# Board_S1_sche.net
KiCad netlist of a schematic drawn in EAGLE
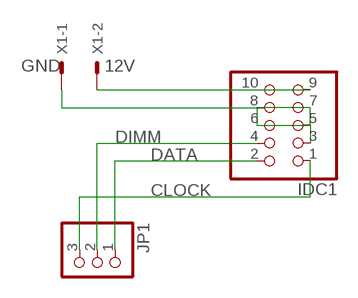
[diagram p0: schematic, sheet 1]

(export (version "E")
  (design (tool "Eeschema 10.0.6"))
  (components
    (comp (ref "IDC1")
      (value "PINHD-2X5")
      (footprint "eagle-import:2X05")
      (libsource (lib "eagle-import") (part "PINHD-2X5"))
    )
    (comp (ref "JP1")
      (value "PINHD-1X3")
      (footprint "eagle-import:1X03")
      (libsource (lib "eagle-import") (part "PINHD-1X3"))
    )
    (comp (ref "X1")
      (value "KK-156-2")
      (footprint "eagle-import:KK-156-2")
      (libsource (lib "eagle-import") (part "KK-156-2"))
    )
  )
  (nets
    (net (code "1") (name "/12V") (class "Default")
      (node (ref "IDC1") (pin "10") (pinfunction "10_10") (pintype "passive"))
      (node (ref "IDC1") (pin "9") (pinfunction "9_9") (pintype "passive"))
      (node (ref "X1") (pin "2") (pinfunction "S_2") (pintype "passive"))
    )
    (net (code "2") (name "/CLOCK") (class "Default")
      (node (ref "IDC1") (pin "1") (pinfunction "1_1") (pintype "passive"))
      (node (ref "JP1") (pin "3") (pinfunction "3_3") (pintype "passive"))
    )
    (net (code "3") (name "/DATA") (class "Default")
      (node (ref "IDC1") (pin "2") (pinfunction "2_2") (pintype "passive"))
      (node (ref "JP1") (pin "1") (pinfunction "1_1") (pintype "passive"))
    )
    (net (code "4") (name "/DIMM") (class "Default")
      (node (ref "IDC1") (pin "4") (pinfunction "4_4") (pintype "passive"))
      (node (ref "JP1") (pin "2") (pinfunction "2_2") (pintype "passive"))
    )
    (net (code "5") (name "/GND") (class "Default")
      (node (ref "IDC1") (pin "3") (pinfunction "3_3") (pintype "passive"))
      (node (ref "IDC1") (pin "5") (pinfunction "5_5") (pintype "passive"))
      (node (ref "IDC1") (pin "6") (pinfunction "6_6") (pintype "passive"))
      (node (ref "IDC1") (pin "7") (pinfunction "7_7") (pintype "passive"))
      (node (ref "IDC1") (pin "8") (pinfunction "8_8") (pintype "passive"))
      (node (ref "X1") (pin "1") (pinfunction "S_1") (pintype "passive"))
    )
  )
)
